# REG_5V.net
KiCad netlist of a schematic drawn in EAGLE
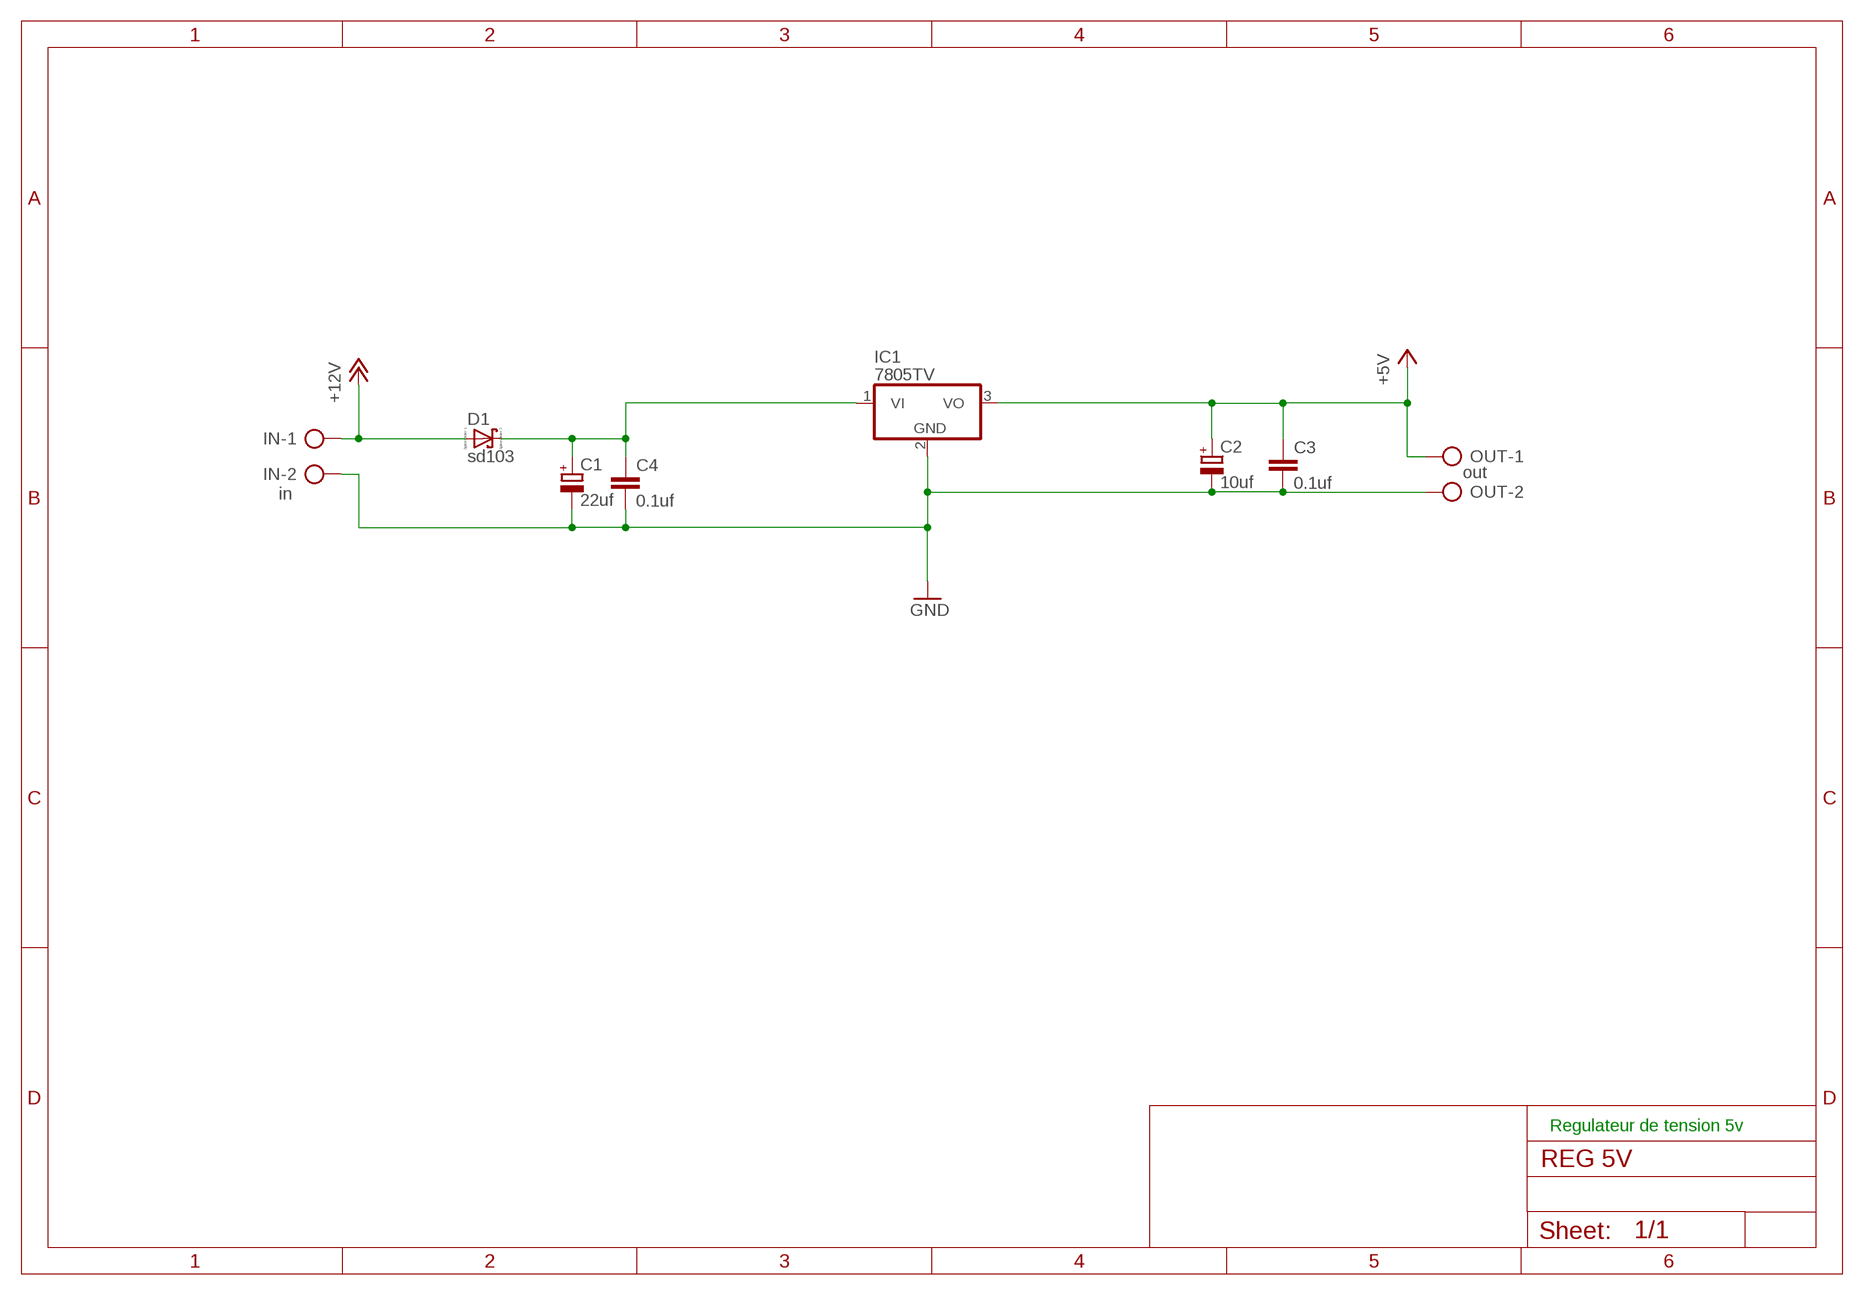
[diagram p0: schematic, sheet 1]

(export (version "E")
  (design (tool "Eeschema 10.0.6"))
  (components
    (comp (ref "C1")
      (value "22uf")
      (footprint "eagle-import:E2,5-5")
      (libsource (lib "eagle-import") (part "CPOL-EUE2.5-5"))
    )
    (comp (ref "C2")
      (value "10uf")
      (footprint "eagle-import:E2,5-5")
      (libsource (lib "eagle-import") (part "CPOL-EUE2.5-5"))
    )
    (comp (ref "C3")
      (value "0.1uf")
      (footprint "eagle-import:C025-024X044")
      (libsource (lib "eagle-import") (part "C-EU025-024X044"))
    )
    (comp (ref "C4")
      (value "0.1uf")
      (footprint "eagle-import:C025-024X044")
      (libsource (lib "eagle-import") (part "C-EU025-024X044"))
    )
    (comp (ref "D1")
      (value "sd103")
      (footprint "eagle-import:DIODE_DO35-7")
      (libsource (lib "eagle-import") (part "SCHOTTKY-DIODEDO35-7"))
    )
    (comp (ref "IC1")
      (value "7805TV")
      (footprint "eagle-import:TO220V")
      (libsource (lib "eagle-import") (part "78TV05"))
    )
    (comp (ref "IN")
      (value "in")
      (footprint "eagle-import:AK500_2")
      (libsource (lib "eagle-import") (part "AK500/2"))
    )
    (comp (ref "OUT")
      (value "out")
      (footprint "eagle-import:AK500_2")
      (libsource (lib "eagle-import") (part "AK500/2"))
    )
  )
  (nets
    (net (code "1") (name "+5V") (class "Default")
      (node (ref "C2") (pin "+") (pinfunction "+_+") (pintype "passive"))
      (node (ref "C3") (pin "1") (pinfunction "1_1") (pintype "passive"))
      (node (ref "IC1") (pin "3") (pinfunction "VO_3") (pintype "passive"))
      (node (ref "OUT") (pin "1") (pinfunction "KL_1") (pintype "passive"))
    )
    (net (code "2") (name "+12V") (class "Default")
      (node (ref "D1") (pin "A") (pinfunction "C_A") (pintype "passive"))
      (node (ref "IN") (pin "1") (pinfunction "KL_1") (pintype "passive"))
    )
    (net (code "3") (name "GND") (class "Default")
      (node (ref "C1") (pin "-") (pinfunction "-_-") (pintype "passive"))
      (node (ref "C2") (pin "-") (pinfunction "-_-") (pintype "passive"))
      (node (ref "C3") (pin "2") (pinfunction "2_2") (pintype "passive"))
      (node (ref "C4") (pin "2") (pinfunction "2_2") (pintype "passive"))
      (node (ref "IC1") (pin "2") (pinfunction "GND_2") (pintype "passive"))
      (node (ref "IN") (pin "2") (pinfunction "KL_2") (pintype "passive"))
      (node (ref "OUT") (pin "2") (pinfunction "KL_2") (pintype "passive"))
    )
    (net (code "4") (name "Net-(D1-A)") (class "Default")
      (node (ref "C1") (pin "+") (pinfunction "+_+") (pintype "passive"))
      (node (ref "C4") (pin "1") (pinfunction "1_1") (pintype "passive"))
      (node (ref "D1") (pin "C") (pinfunction "A_C") (pintype "passive"))
      (node (ref "IC1") (pin "1") (pinfunction "VI_1") (pintype "input"))
    )
  )
)
